# optical_sensor_v1_1.net
KiCad netlist of a schematic drawn in Altium Designer
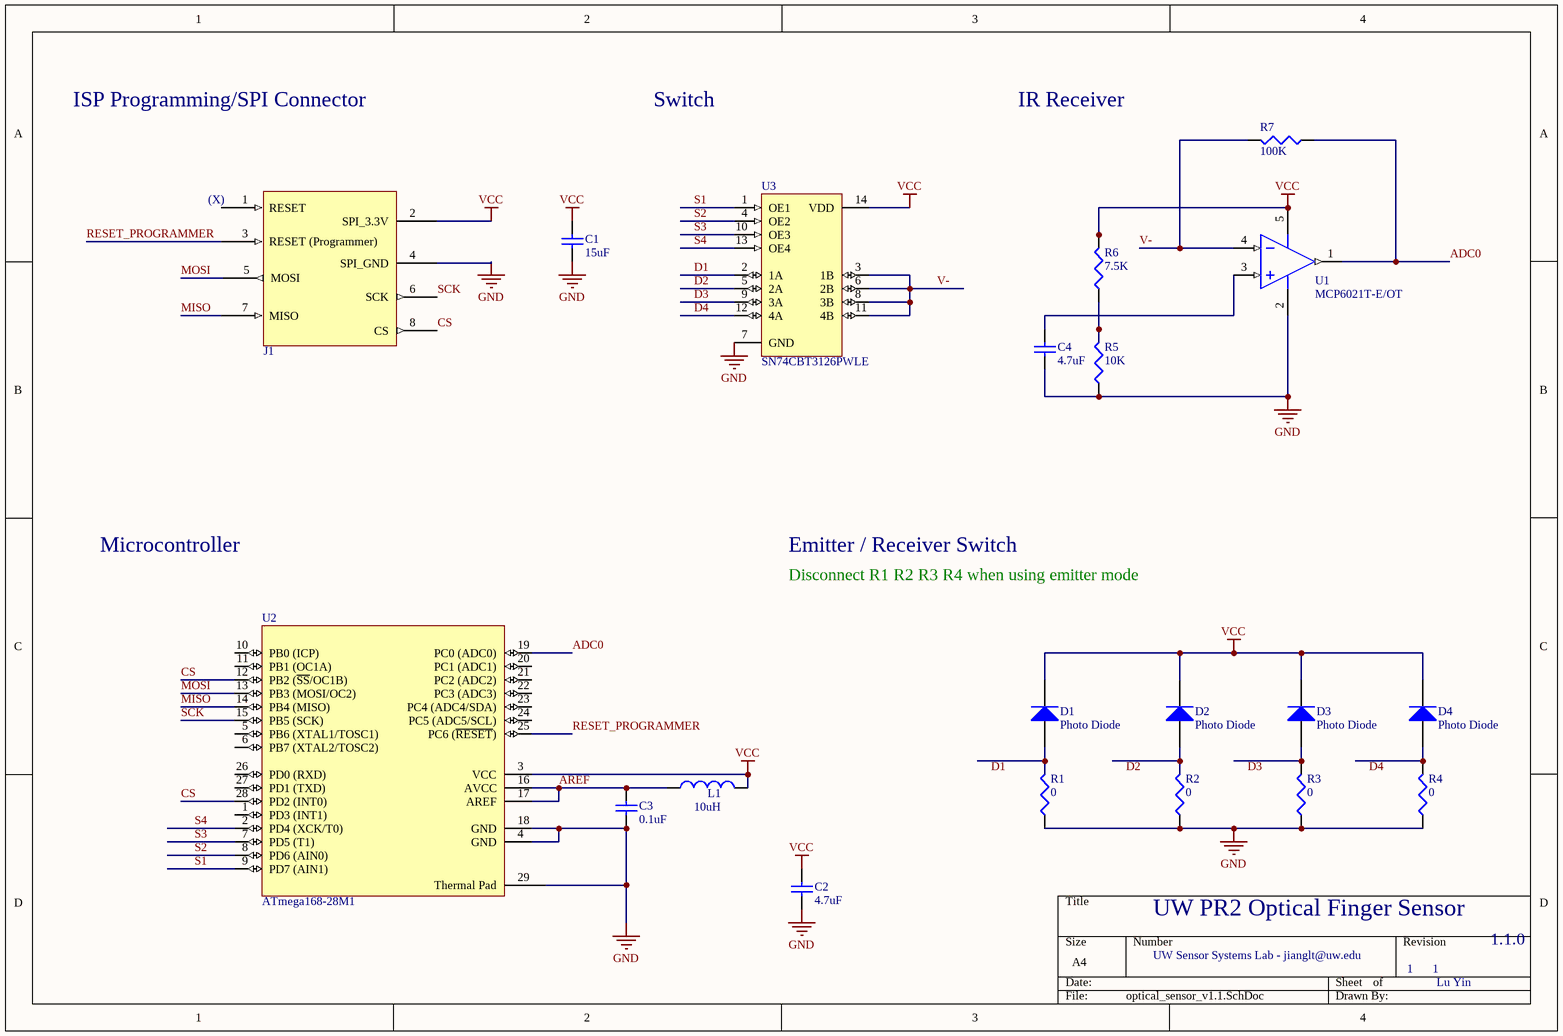
[diagram p0: optical_sensor_v1.1.SchDoc]

(export (version "E")
  (design (tool "Eeschema 10.0.6"))
  (components
    (comp (ref "C1")
      (value "15uF")
      (footprint "CAPC1608N")
      (description "Capacitor (Semiconductor SIM Model)")
      (fields (field (name "Comment") "Cap Semi") (field (name "PUBLISHER") "Altium Limited"))
      (libsource (lib "Miscellaneous Devices") (part "Cap Semi"))
    )
    (comp (ref "C2")
      (value "4.7uF")
      (footprint "CAPC1608N")
      (description "Capacitor (Semiconductor SIM Model)")
      (fields (field (name "Comment") "Cap Semi") (field (name "PUBLISHER") "Altium Limited"))
      (libsource (lib "Miscellaneous Devices") (part "Cap Semi"))
    )
    (comp (ref "C3")
      (value "0.1uF")
      (footprint "CAPC1608N")
      (description "Capacitor (Semiconductor SIM Model)")
      (fields (field (name "Comment") "BypassCap") (field (name "PUBLISHER") "Altium Limited"))
      (libsource (lib "Miscellaneous Devices") (part "Cap Semi"))
    )
    (comp (ref "C4")
      (value "4.7uF")
      (footprint "CAPC1608N")
      (description "Capacitor (Semiconductor SIM Model)")
      (fields (field (name "Comment") "Cap Semi") (field (name "PUBLISHER") "Altium Limited"))
      (libsource (lib "Miscellaneous Devices") (part "Cap Semi"))
    )
    (comp (ref "D1")
      (value "Photo Diode")
      (footprint "Vishay VEMD/VSMB footprint")
      (description "Default Diode")
      (fields (field (name "PUBLISHER") "Altium Limited"))
      (libsource (lib "Miscellaneous Devices") (part "Diode"))
    )
    (comp (ref "D2")
      (value "Photo Diode")
      (footprint "Vishay VEMD/VSMB footprint")
      (description "Default Diode")
      (fields (field (name "PUBLISHER") "Altium Limited"))
      (libsource (lib "Miscellaneous Devices") (part "Diode"))
    )
    (comp (ref "D3")
      (value "Photo Diode")
      (footprint "Vishay VEMD/VSMB footprint")
      (description "Default Diode")
      (fields (field (name "PUBLISHER") "Altium Limited"))
      (libsource (lib "Miscellaneous Devices") (part "Diode"))
    )
    (comp (ref "D4")
      (value "Photo Diode")
      (footprint "Vishay VEMD/VSMB footprint")
      (description "Default Diode")
      (fields (field (name "PUBLISHER") "Altium Limited"))
      (libsource (lib "Miscellaneous Devices") (part "Diode"))
    )
    (comp (ref "J1")
      (value "FFC 8-PIN Connector (1mm)")
      (footprint "Hirose FFC connector 8-Pin")
      (description "FFC 8-PIN Connector (1mm) (SMT)")
      (libsource (lib "UW_PR2_FINERTIP_COMPONENTS") (part "FFC Connector-8Pin-SMT-1mm"))
    )
    (comp (ref "L1")
      (value "10uH")
      (footprint "INDC1608N")
      (description "Inductor")
      (fields (field (name "PUBLISHER") "Altium Limited"))
      (libsource (lib "Miscellaneous Devices") (part "Inductor"))
    )
    (comp (ref "R1")
      (value "0")
      (footprint "RESC1608N")
      (description "Resistor")
      (fields (field (name "Comment") "Rlevel") (field (name "PUBLISHER") "Altium Limited"))
      (libsource (lib "Miscellaneous Devices") (part "Res3"))
    )
    (comp (ref "R2")
      (value "0")
      (footprint "RESC1608N")
      (description "Resistor")
      (fields (field (name "Comment") "Rlevel") (field (name "PUBLISHER") "Altium Limited"))
      (libsource (lib "Miscellaneous Devices") (part "Res3"))
    )
    (comp (ref "R3")
      (value "0")
      (footprint "RESC1608N")
      (description "Resistor")
      (fields (field (name "Comment") "Rlevel") (field (name "PUBLISHER") "Altium Limited"))
      (libsource (lib "Miscellaneous Devices") (part "Res3"))
    )
    (comp (ref "R4")
      (value "0")
      (footprint "RESC1608N")
      (description "Resistor")
      (fields (field (name "Comment") "Rlevel") (field (name "PUBLISHER") "Altium Limited"))
      (libsource (lib "Miscellaneous Devices") (part "Res3"))
    )
    (comp (ref "R5")
      (value "10K")
      (footprint "RESC1608N")
      (description "Resistor")
      (fields (field (name "Comment") "Rlevel") (field (name "PUBLISHER") "Altium Limited"))
      (libsource (lib "Miscellaneous Devices") (part "Res3"))
    )
    (comp (ref "R6")
      (value "7.5K")
      (footprint "RESC1608N")
      (description "Resistor")
      (fields (field (name "Comment") "Rlevel") (field (name "PUBLISHER") "Altium Limited"))
      (libsource (lib "Miscellaneous Devices") (part "Res3"))
    )
    (comp (ref "R7")
      (value "100K")
      (footprint "RESC1608N")
      (description "Resistor")
      (fields (field (name "Comment") "Rlevel") (field (name "PUBLISHER") "Altium Limited"))
      (libsource (lib "Miscellaneous Devices") (part "Res3"))
    )
    (comp (ref "U1")
      (value "MCP6021T-E/OT")
      (footprint "SOT-23-OT5_N")
      (fields (field (name "PUBLISHER") "Altium Limited"))
      (libsource (lib "Microchip Linear Devices") (part "MCP6021T-E/OT"))
    )
    (comp (ref "U2")
      (value "ATmega168-28M1")
      (description "8-Bit AVR Microcontroller with 8K Bytes of In-System Programmable Flash Memory")
      (fields (field (name "PUBLISHER") "Altium Limited"))
      (libsource (lib "UW_PR2_FINERTIP_COMPONENTS") (part "ATmega168-28M1"))
    )
    (comp (ref "U3")
      (value "SN74CBT3126PWLE")
      (footprint "PW014_N")
      (description "Quadruple FET Bus Switch")
      (fields (field (name "PUBLISHER") "Altium Limited"))
      (libsource (lib "TI Logic Switch") (part "SN74CBT3126PWLE"))
    )
  )
  (nets
    (net (code "1") (name "/ADC0") (class "Default")
      (node (ref "R7") (pin "1") (pinfunction "1_1") (pintype "passive"))
      (node (ref "U1") (pin "1") (pinfunction "VOUT_1") (pintype "output"))
      (node (ref "U2") (pin "19") (pinfunction "PC0_(ADC0)_19") (pintype "bidirectional"))
    )
    (net (code "2") (name "/AREF") (class "Default")
      (node (ref "C3") (pin "2") (pinfunction "2_2") (pintype "passive"))
      (node (ref "L1") (pin "1") (pinfunction "1_1") (pintype "passive"))
      (node (ref "U2") (pin "16") (pinfunction "AVCC_16") (pintype "power_in"))
      (node (ref "U2") (pin "17") (pinfunction "AREF_17") (pintype "passive"))
    )
    (net (code "3") (name "/CS") (class "Default")
      (node (ref "J1") (pin "8") (pinfunction "CS_8") (pintype "output"))
      (node (ref "U2") (pin "12") (pinfunction "PB2_(~{SS}/OC1B)_12") (pintype "bidirectional"))
      (node (ref "U2") (pin "28") (pinfunction "PD2_(INT0)_28") (pintype "bidirectional"))
    )
    (net (code "4") (name "/D1") (class "Default")
      (node (ref "U3") (pin "2") (pinfunction "1A_2") (pintype "bidirectional"))
    )
    (net (code "5") (name "/D2") (class "Default")
      (node (ref "U3") (pin "5") (pinfunction "2A_5") (pintype "bidirectional"))
    )
    (net (code "6") (name "/D3") (class "Default")
      (node (ref "U3") (pin "9") (pinfunction "3A_9") (pintype "bidirectional"))
    )
    (net (code "7") (name "/D4") (class "Default")
      (node (ref "U3") (pin "12") (pinfunction "4A_12") (pintype "bidirectional"))
    )
    (net (code "8") (name "/MISO") (class "Default")
      (node (ref "J1") (pin "7") (pinfunction "MISO_7") (pintype "input"))
      (node (ref "U2") (pin "14") (pinfunction "PB4_(MISO)_14") (pintype "bidirectional"))
    )
    (net (code "9") (name "/MOSI") (class "Default")
      (node (ref "J1") (pin "5") (pinfunction "MOSI_5") (pintype "output"))
      (node (ref "U2") (pin "13") (pinfunction "PB3_(MOSI/OC2)_13") (pintype "bidirectional"))
    )
    (net (code "10") (name "/RESET_PROGRAMMER") (class "Default")
      (node (ref "J1") (pin "3") (pinfunction "RESET_(Programmer)_3") (pintype "input"))
      (node (ref "U2") (pin "25") (pinfunction "PC6_(~{RESET})_25") (pintype "bidirectional"))
    )
    (net (code "11") (name "/S1") (class "Default")
      (node (ref "U2") (pin "9") (pinfunction "PD7_(AIN1)_9") (pintype "bidirectional"))
      (node (ref "U3") (pin "1") (pinfunction "OE1_1") (pintype "input"))
    )
    (net (code "12") (name "/S2") (class "Default")
      (node (ref "U2") (pin "8") (pinfunction "PD6_(AIN0)_8") (pintype "bidirectional"))
      (node (ref "U3") (pin "4") (pinfunction "OE2_4") (pintype "input"))
    )
    (net (code "13") (name "/S3") (class "Default")
      (node (ref "U2") (pin "7") (pinfunction "PD5_(T1)_7") (pintype "bidirectional"))
      (node (ref "U3") (pin "10") (pinfunction "OE3_10") (pintype "input"))
    )
    (net (code "14") (name "/S4") (class "Default")
      (node (ref "U2") (pin "2") (pinfunction "PD4_(XCK/T0)_2") (pintype "bidirectional"))
      (node (ref "U3") (pin "13") (pinfunction "OE4_13") (pintype "input"))
    )
    (net (code "15") (name "/SCK") (class "Default")
      (node (ref "J1") (pin "6") (pinfunction "SCK_6") (pintype "output"))
      (node (ref "U2") (pin "15") (pinfunction "PB5_(SCK)_15") (pintype "bidirectional"))
    )
    (net (code "16") (name "/V-") (class "Default")
      (node (ref "R7") (pin "2") (pinfunction "2_2") (pintype "passive"))
      (node (ref "U1") (pin "4") (pinfunction "VIN-_4") (pintype "input"))
      (node (ref "U3") (pin "11") (pinfunction "4B_11") (pintype "bidirectional"))
      (node (ref "U3") (pin "3") (pinfunction "1B_3") (pintype "bidirectional"))
      (node (ref "U3") (pin "6") (pinfunction "2B_6") (pintype "bidirectional"))
      (node (ref "U3") (pin "8") (pinfunction "3B_8") (pintype "bidirectional"))
    )
    (net (code "17") (name "GND") (class "Default")
      (node (ref "C1") (pin "2") (pinfunction "2_2") (pintype "passive"))
      (node (ref "C2") (pin "2") (pinfunction "2_2") (pintype "passive"))
      (node (ref "C3") (pin "1") (pinfunction "1_1") (pintype "passive"))
      (node (ref "C4") (pin "2") (pinfunction "2_2") (pintype "passive"))
      (node (ref "J1") (pin "4") (pinfunction "SPI_GND_4") (pintype "power_in"))
      (node (ref "R1") (pin "1") (pinfunction "1_1") (pintype "passive"))
      (node (ref "R2") (pin "1") (pinfunction "1_1") (pintype "passive"))
      (node (ref "R3") (pin "1") (pinfunction "1_1") (pintype "passive"))
      (node (ref "R4") (pin "1") (pinfunction "1_1") (pintype "passive"))
      (node (ref "R5") (pin "1") (pinfunction "1_1") (pintype "passive"))
      (node (ref "U1") (pin "2") (pinfunction "VSS_2") (pintype "power_in"))
      (node (ref "U2") (pin "18") (pinfunction "GND_18") (pintype "power_in"))
      (node (ref "U2") (pin "29") (pinfunction "Thermal_Pad_29") (pintype "power_in"))
      (node (ref "U2") (pin "4") (pinfunction "GND_4") (pintype "power_in"))
      (node (ref "U3") (pin "7") (pinfunction "GND_7") (pintype "power_in"))
    )
    (net (code "18") (name "Net-(D1-A)") (class "Default")
      (node (ref "D1") (pin "1") (pinfunction "A_1") (pintype "passive"))
      (node (ref "R1") (pin "2") (pinfunction "2_2") (pintype "passive"))
    )
    (net (code "19") (name "Net-(D2-A)") (class "Default")
      (node (ref "D2") (pin "1") (pinfunction "A_1") (pintype "passive"))
      (node (ref "R2") (pin "2") (pinfunction "2_2") (pintype "passive"))
    )
    (net (code "20") (name "Net-(D3-A)") (class "Default")
      (node (ref "D3") (pin "1") (pinfunction "A_1") (pintype "passive"))
      (node (ref "R3") (pin "2") (pinfunction "2_2") (pintype "passive"))
    )
    (net (code "21") (name "Net-(D4-A)") (class "Default")
      (node (ref "D4") (pin "1") (pinfunction "A_1") (pintype "passive"))
      (node (ref "R4") (pin "2") (pinfunction "2_2") (pintype "passive"))
    )
    (net (code "22") (name "Net-(R5-Pad2)") (class "Default")
      (node (ref "R5") (pin "2") (pinfunction "2_2") (pintype "passive"))
      (node (ref "R6") (pin "1") (pinfunction "1_1") (pintype "passive"))
    )
    (net (code "23") (name "Net-(U1-VIN+)") (class "Default")
      (node (ref "C4") (pin "1") (pinfunction "1_1") (pintype "passive"))
      (node (ref "U1") (pin "3") (pinfunction "VIN+_3") (pintype "input"))
    )
    (net (code "24") (name "VCC") (class "Default")
      (node (ref "C1") (pin "1") (pinfunction "1_1") (pintype "passive"))
      (node (ref "C2") (pin "1") (pinfunction "1_1") (pintype "passive"))
      (node (ref "D1") (pin "2") (pinfunction "K_2") (pintype "passive"))
      (node (ref "D2") (pin "2") (pinfunction "K_2") (pintype "passive"))
      (node (ref "D3") (pin "2") (pinfunction "K_2") (pintype "passive"))
      (node (ref "D4") (pin "2") (pinfunction "K_2") (pintype "passive"))
      (node (ref "J1") (pin "2") (pinfunction "SPI_3.3V_2") (pintype "power_in"))
      (node (ref "L1") (pin "2") (pinfunction "2_2") (pintype "passive"))
      (node (ref "R6") (pin "2") (pinfunction "2_2") (pintype "passive"))
      (node (ref "U1") (pin "5") (pinfunction "VDD_5") (pintype "power_in"))
      (node (ref "U2") (pin "3") (pinfunction "VCC_3") (pintype "power_in"))
      (node (ref "U3") (pin "14") (pinfunction "VDD_14") (pintype "power_in"))
    )
    (net (code "25") (name "unconnected-(J1-RESET-Pad1)") (class "Default")
      (node (ref "J1") (pin "1") (pinfunction "RESET_1") (pintype "input"))
    )
    (net (code "26") (name "unconnected-(U2-PB0_(ICP)-Pad10)") (class "Default")
      (node (ref "U2") (pin "10") (pinfunction "PB0_(ICP)_10") (pintype "bidirectional"))
    )
    (net (code "27") (name "unconnected-(U2-PB1_(OC1A)-Pad11)") (class "Default")
      (node (ref "U2") (pin "11") (pinfunction "PB1_(OC1A)_11") (pintype "bidirectional"))
    )
    (net (code "28") (name "unconnected-(U2-PB6_(XTAL1{slash}TOSC1)-Pad5)") (class "Default")
      (node (ref "U2") (pin "5") (pinfunction "PB6_(XTAL1/TOSC1)_5") (pintype "bidirectional"))
    )
    (net (code "29") (name "unconnected-(U2-PB7_(XTAL2{slash}TOSC2)-Pad6)") (class "Default")
      (node (ref "U2") (pin "6") (pinfunction "PB7_(XTAL2/TOSC2)_6") (pintype "bidirectional"))
    )
    (net (code "30") (name "unconnected-(U2-PC1_(ADC1)-Pad20)") (class "Default")
      (node (ref "U2") (pin "20") (pinfunction "PC1_(ADC1)_20") (pintype "bidirectional"))
    )
    (net (code "31") (name "unconnected-(U2-PC2_(ADC2)-Pad21)") (class "Default")
      (node (ref "U2") (pin "21") (pinfunction "PC2_(ADC2)_21") (pintype "bidirectional"))
    )
    (net (code "32") (name "unconnected-(U2-PC3_(ADC3)-Pad22)") (class "Default")
      (node (ref "U2") (pin "22") (pinfunction "PC3_(ADC3)_22") (pintype "bidirectional"))
    )
    (net (code "33") (name "unconnected-(U2-PC4_(ADC4{slash}SDA)-Pad23)") (class "Default")
      (node (ref "U2") (pin "23") (pinfunction "PC4_(ADC4/SDA)_23") (pintype "bidirectional"))
    )
    (net (code "34") (name "unconnected-(U2-PC5_(ADC5{slash}SCL)-Pad24)") (class "Default")
      (node (ref "U2") (pin "24") (pinfunction "PC5_(ADC5/SCL)_24") (pintype "bidirectional"))
    )
    (net (code "35") (name "unconnected-(U2-PD0_(RXD)-Pad26)") (class "Default")
      (node (ref "U2") (pin "26") (pinfunction "PD0_(RXD)_26") (pintype "bidirectional"))
    )
    (net (code "36") (name "unconnected-(U2-PD1_(TXD)-Pad27)") (class "Default")
      (node (ref "U2") (pin "27") (pinfunction "PD1_(TXD)_27") (pintype "bidirectional"))
    )
    (net (code "37") (name "unconnected-(U2-PD3_(INT1)-Pad1)") (class "Default")
      (node (ref "U2") (pin "1") (pinfunction "PD3_(INT1)_1") (pintype "bidirectional"))
    )
  )
)
